# Knot_Thing_USB_Power.net
KiCad netlist of a schematic drawn in Altium Designer
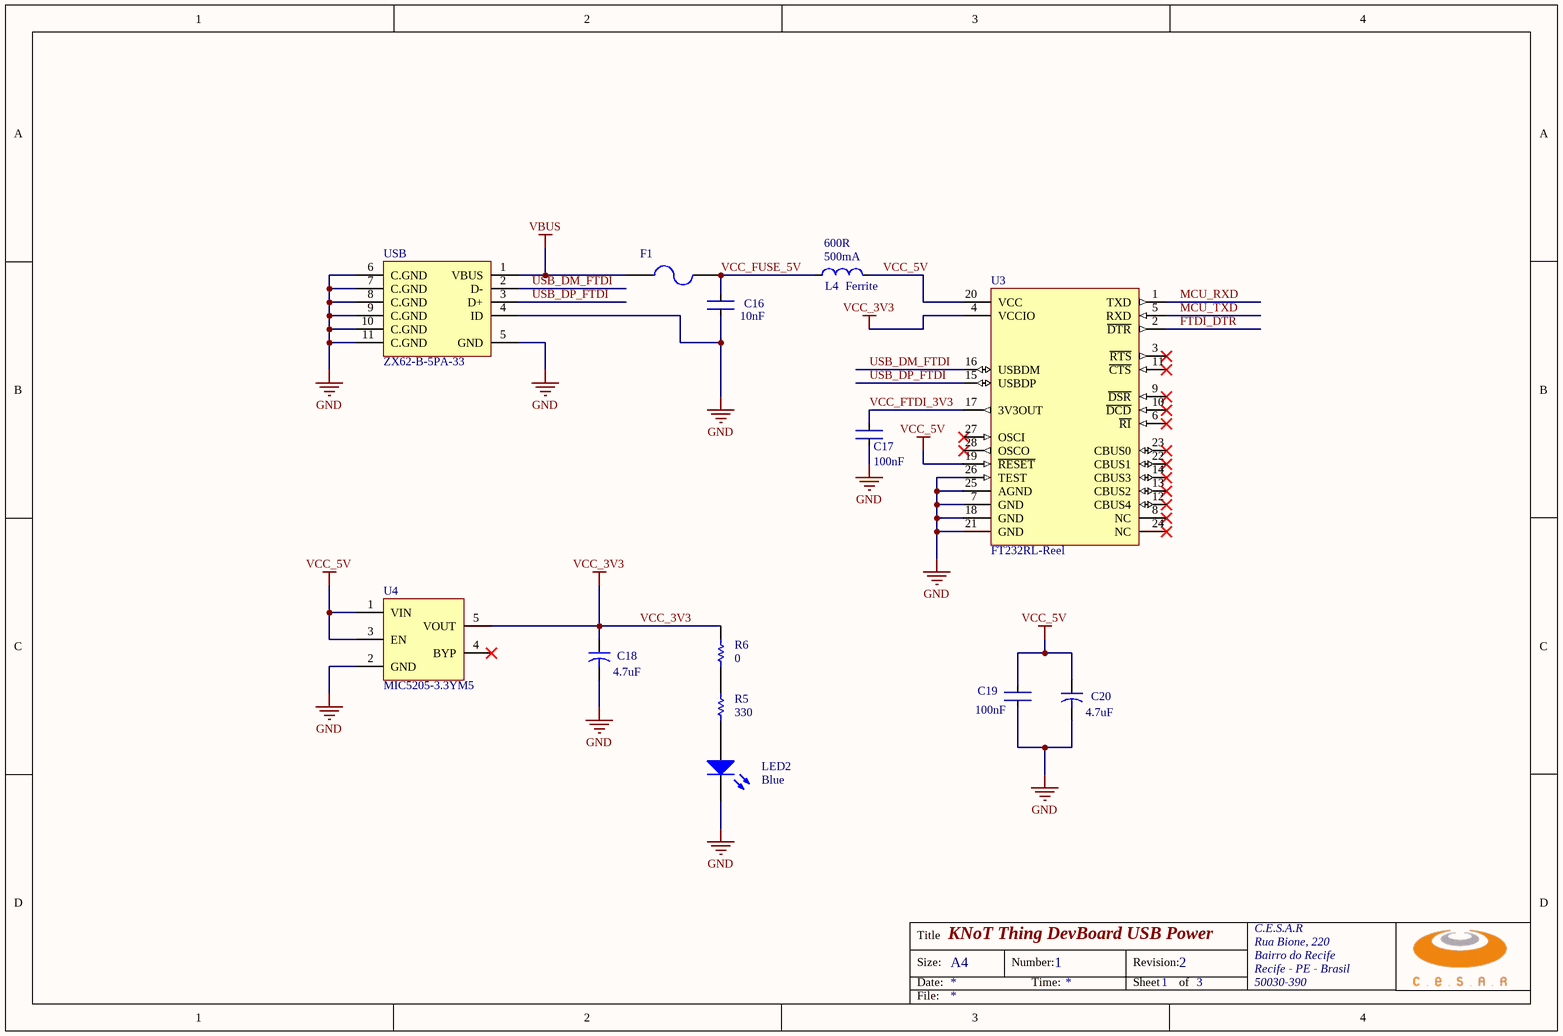
[diagram p0: Knot_Thing_USB_Power.SchDoc]

(export (version "E")
  (design (tool "Eeschema 10.0.6"))
  (components
    (comp (ref "C16")
      (value "10nF")
      (footprint "CAPC1005L")
      (description "Chip Capacitor 0402 (1005 metric)")
      (fields (field (name "Comment") "Cap_0402"))
      (libsource (lib "KNoT_Thing") (part "Capacitor_0402"))
    )
    (comp (ref "C17")
      (value "100nF")
      (footprint "CAPC1005L")
      (description "Chip Capacitor 0402 (1005 metric)")
      (fields (field (name "Comment") "Cap_0402"))
      (libsource (lib "KNoT_Thing") (part "Capacitor_0402"))
    )
    (comp (ref "C18")
      (value "4.7uF")
      (footprint "CAPC1608L")
      (description "4.7µF 10V Ceramic Capacitor X5R 0603")
      (fields (field (name "Comment") "Cap0603") (field (name "PUBLISHER") "Altium Limited"))
      (libsource (lib "KNoT_Thing") (part "Cap0603"))
    )
    (comp (ref "C19")
      (value "100nF")
      (footprint "CAPC1005L")
      (description "Chip Capacitor 0402 (1005 metric)")
      (fields (field (name "Comment") "Cap_0402"))
      (libsource (lib "KNoT_Thing") (part "Capacitor_0402"))
    )
    (comp (ref "C20")
      (value "4.7uF")
      (footprint "CAPC1608L")
      (description "4.7µF 10V Ceramic Capacitor X5R 0603")
      (fields (field (name "Comment") "Cap0603") (field (name "PUBLISHER") "Altium Limited"))
      (libsource (lib "KNoT_Thing") (part "Cap0603"))
    )
    (comp (ref "F1")
      (value "0402L050SLKR")
      (footprint "0805L")
      (description "PTC Resettable Fuse 6V 500mA Ih Surface Mount 0402 (1005 Metric), Concave")
      (libsource (lib "KNoT_Thing") (part "Fuse 2"))
    )
    (comp (ref "L4")
      (value "Ferrite")
      (footprint "0603-cap")
      (description "BLM18AG121SN1 FERRITE 120 OHM 500MA 0603")
      (fields (field (name "RES") "600R") (field (name "CUR") "500mA"))
      (libsource (lib "KNoT_Thing") (part "Ferrite"))
    )
    (comp (ref "LED2")
      (value "LED 0603")
      (footprint "0603_LED")
      (description "LED SMD 0603")
      (fields (field (name "COLOR") "Blue"))
      (libsource (lib "KNoT_Thing") (part "LED 0603"))
    )
    (comp (ref "R5")
      (value "330")
      (footprint "CAPC1005L")
      (fields (field (name "Comment") "RES_0402"))
      (libsource (lib "KNoT_Thing") (part "RES_0402"))
    )
    (comp (ref "R6")
      (value "0")
      (footprint "CAPC1005L")
      (fields (field (name "Comment") "RES_0402"))
      (libsource (lib "KNoT_Thing") (part "RES_0402"))
    )
    (comp (ref "U3")
      (value "FT232RL-Reel")
      (footprint "SSOP-28_N")
      (description "USB UART Asynchronous Serial Data Transfer Chip, 28-pin SSOP, Tape and Reel")
      (fields (field (name "MANUFACTURER") "FTDI"))
      (libsource (lib "KNoT_Thing") (part "FT232RL-Reel"))
    )
    (comp (ref "U4")
      (value "MIC5205-3.3YM5")
      (footprint "SOT23-5")
      (description "Voltage Regulator")
      (libsource (lib "KNoT_Thing") (part "MIC5205-3.3YM5"))
    )
    (comp (ref "USB")
      (value "ZX62-B-5PA-33")
      (footprint "Micro USB b")
      (description "USB Connector")
      (libsource (lib "KNoT_Thing") (part "ZX62-B-5PA-33"))
    )
  )
  (nets
    (net (code "1") (name "/FTDI_DTR") (class "Default")
      (node (ref "U3") (pin "2") (pinfunction "~{DTR}_2") (pintype "output"))
    )
    (net (code "2") (name "/MCU_RXD") (class "Default")
      (node (ref "U3") (pin "1") (pinfunction "TXD_1") (pintype "output"))
    )
    (net (code "3") (name "/MCU_TXD") (class "Default")
      (node (ref "U3") (pin "5") (pinfunction "RXD_5") (pintype "input"))
    )
    (net (code "4") (name "/USB_DM_FTDI") (class "Default")
      (node (ref "U3") (pin "16") (pinfunction "USBDM_16") (pintype "bidirectional"))
      (node (ref "USB") (pin "2") (pinfunction "D-_2") (pintype "passive"))
    )
    (net (code "5") (name "/USB_DP_FTDI") (class "Default")
      (node (ref "U3") (pin "15") (pinfunction "USBDP_15") (pintype "bidirectional"))
      (node (ref "USB") (pin "3") (pinfunction "D+_3") (pintype "passive"))
    )
    (net (code "6") (name "/VCC_FTDI_3V3") (class "Default")
      (node (ref "C17") (pin "1") (pinfunction "1_1") (pintype "passive"))
      (node (ref "U3") (pin "17") (pinfunction "3V3OUT_17") (pintype "output"))
    )
    (net (code "7") (name "/VCC_FUSE_5V") (class "Default")
      (node (ref "C16") (pin "2") (pinfunction "0_2") (pintype "passive"))
      (node (ref "F1") (pin "2") (pinfunction "2_2") (pintype "passive"))
      (node (ref "L4") (pin "1") (pinfunction "1_1") (pintype "passive"))
    )
    (net (code "8") (name "GND") (class "Default")
      (node (ref "C16") (pin "1") (pinfunction "1_1") (pintype "passive"))
      (node (ref "C17") (pin "2") (pinfunction "0_2") (pintype "passive"))
      (node (ref "C18") (pin "2") (pinfunction "2_2") (pintype "passive"))
      (node (ref "C19") (pin "2") (pinfunction "0_2") (pintype "passive"))
      (node (ref "C20") (pin "2") (pinfunction "2_2") (pintype "passive"))
      (node (ref "LED2") (pin "2") (pinfunction "K_2") (pintype "passive"))
      (node (ref "U3") (pin "18") (pinfunction "GND_18") (pintype "power_in"))
      (node (ref "U3") (pin "21") (pinfunction "GND_21") (pintype "power_in"))
      (node (ref "U3") (pin "25") (pinfunction "AGND_25") (pintype "power_in"))
      (node (ref "U3") (pin "26") (pinfunction "TEST_26") (pintype "input"))
      (node (ref "U3") (pin "7") (pinfunction "GND_7") (pintype "power_in"))
      (node (ref "U4") (pin "2") (pinfunction "GND_2") (pintype "passive"))
      (node (ref "USB") (pin "10") (pinfunction "C.GND_10") (pintype "passive"))
      (node (ref "USB") (pin "11") (pinfunction "C.GND_11") (pintype "passive"))
      (node (ref "USB") (pin "4") (pinfunction "ID_4") (pintype "passive"))
      (node (ref "USB") (pin "5") (pinfunction "GND_5") (pintype "passive"))
      (node (ref "USB") (pin "6") (pinfunction "C.GND_6") (pintype "passive"))
      (node (ref "USB") (pin "7") (pinfunction "C.GND_7") (pintype "passive"))
      (node (ref "USB") (pin "8") (pinfunction "C.GND_8") (pintype "passive"))
      (node (ref "USB") (pin "9") (pinfunction "C.GND_9") (pintype "passive"))
    )
    (net (code "9") (name "Net-(LED2-A)") (class "Default")
      (node (ref "LED2") (pin "1") (pinfunction "A_1") (pintype "passive"))
      (node (ref "R5") (pin "1") (pinfunction "1_1") (pintype "passive"))
    )
    (net (code "10") (name "Net-(R5-Pad2)") (class "Default")
      (node (ref "R5") (pin "2") (pinfunction "2_2") (pintype "passive"))
      (node (ref "R6") (pin "1") (pinfunction "1_1") (pintype "passive"))
    )
    (net (code "11") (name "VBUS") (class "Default")
      (node (ref "F1") (pin "1") (pinfunction "1_1") (pintype "passive"))
      (node (ref "USB") (pin "1") (pinfunction "VBUS_1") (pintype "passive"))
    )
    (net (code "12") (name "VCC_3V3") (class "Default")
      (node (ref "C18") (pin "1") (pinfunction "1_1") (pintype "passive"))
      (node (ref "R6") (pin "2") (pinfunction "2_2") (pintype "passive"))
      (node (ref "U3") (pin "4") (pinfunction "VCCIO_4") (pintype "power_in"))
      (node (ref "U4") (pin "5") (pinfunction "VOUT_5") (pintype "passive"))
    )
    (net (code "13") (name "VCC_5V") (class "Default")
      (node (ref "C19") (pin "1") (pinfunction "1_1") (pintype "passive"))
      (node (ref "C20") (pin "1") (pinfunction "1_1") (pintype "passive"))
      (node (ref "L4") (pin "2") (pinfunction "2_2") (pintype "passive"))
      (node (ref "U3") (pin "19") (pinfunction "~{RESET}_19") (pintype "input"))
      (node (ref "U3") (pin "20") (pinfunction "VCC_20") (pintype "power_in"))
      (node (ref "U4") (pin "1") (pinfunction "VIN_1") (pintype "passive"))
      (node (ref "U4") (pin "3") (pinfunction "EN_3") (pintype "passive"))
    )
    (net (code "14") (name "unconnected-(U3-CBUS0-Pad23)") (class "Default")
      (node (ref "U3") (pin "23") (pinfunction "CBUS0_23") (pintype "bidirectional+no_connect"))
    )
    (net (code "15") (name "unconnected-(U3-CBUS1-Pad22)") (class "Default")
      (node (ref "U3") (pin "22") (pinfunction "CBUS1_22") (pintype "bidirectional+no_connect"))
    )
    (net (code "16") (name "unconnected-(U3-CBUS2-Pad13)") (class "Default")
      (node (ref "U3") (pin "13") (pinfunction "CBUS2_13") (pintype "bidirectional+no_connect"))
    )
    (net (code "17") (name "unconnected-(U3-CBUS3-Pad14)") (class "Default")
      (node (ref "U3") (pin "14") (pinfunction "CBUS3_14") (pintype "bidirectional+no_connect"))
    )
    (net (code "18") (name "unconnected-(U3-CBUS4-Pad12)") (class "Default")
      (node (ref "U3") (pin "12") (pinfunction "CBUS4_12") (pintype "bidirectional+no_connect"))
    )
    (net (code "19") (name "unconnected-(U3-NC-Pad8)") (class "Default")
      (node (ref "U3") (pin "8") (pinfunction "NC_8") (pintype "passive+no_connect"))
    )
    (net (code "20") (name "unconnected-(U3-NC-Pad24)") (class "Default")
      (node (ref "U3") (pin "24") (pinfunction "NC_24") (pintype "passive+no_connect"))
    )
    (net (code "21") (name "unconnected-(U3-OSCI-Pad27)") (class "Default")
      (node (ref "U3") (pin "27") (pinfunction "OSCI_27") (pintype "input+no_connect"))
    )
    (net (code "22") (name "unconnected-(U3-OSCO-Pad28)") (class "Default")
      (node (ref "U3") (pin "28") (pinfunction "OSCO_28") (pintype "output+no_connect"))
    )
    (net (code "23") (name "unconnected-(U3-~{CTS}-Pad11)") (class "Default")
      (node (ref "U3") (pin "11") (pinfunction "~{CTS}_11") (pintype "input+no_connect"))
    )
    (net (code "24") (name "unconnected-(U3-~{DCD}-Pad10)") (class "Default")
      (node (ref "U3") (pin "10") (pinfunction "~{DCD}_10") (pintype "input+no_connect"))
    )
    (net (code "25") (name "unconnected-(U3-~{DSR}-Pad9)") (class "Default")
      (node (ref "U3") (pin "9") (pinfunction "~{DSR}_9") (pintype "input+no_connect"))
    )
    (net (code "26") (name "unconnected-(U3-~{RI}-Pad6)") (class "Default")
      (node (ref "U3") (pin "6") (pinfunction "~{RI}_6") (pintype "input+no_connect"))
    )
    (net (code "27") (name "unconnected-(U3-~{RTS}-Pad3)") (class "Default")
      (node (ref "U3") (pin "3") (pinfunction "~{RTS}_3") (pintype "output+no_connect"))
    )
    (net (code "28") (name "unconnected-(U4-BYP-Pad4)") (class "Default")
      (node (ref "U4") (pin "4") (pinfunction "BYP_4") (pintype "passive+no_connect"))
    )
  )
)
